# design.net
KiCad netlist of a schematic drawn in Altium Designer
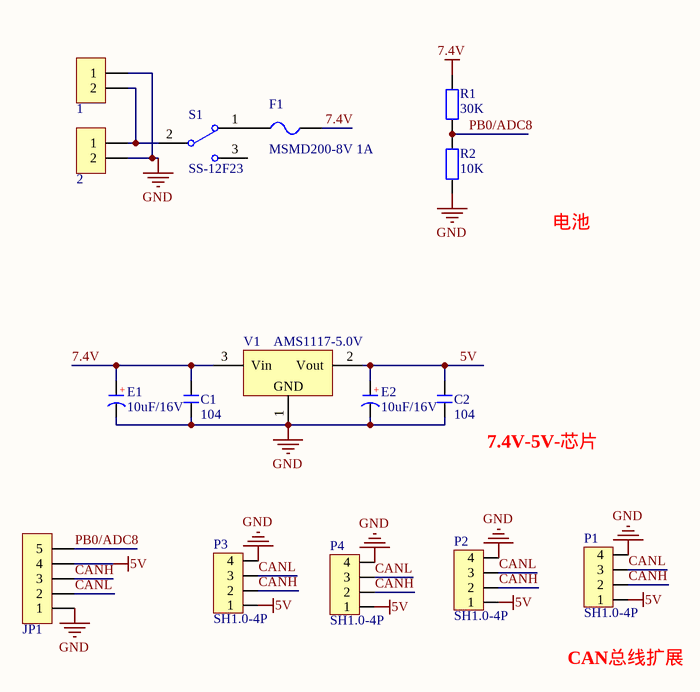
[diagram p0: 电源板.SchDoc]

(export (version "E")
  (design (tool "Eeschema 10.0.6"))
  (components
    (comp (ref "1")
      (value "HDR-1X2")
      (footprint "XH2.54-WI-2P")
      (description "2P接插件")
      (fields (field (name "版权归属") "封装库来自淘宝 ID：黄晶宝石"))
      (libsource (lib "5.3 - 接插件-脚距2.54 (100mil) ") (part "Header 2"))
    )
    (comp (ref "2")
      (value "HDR-1X2")
      (footprint "XH2.54-WI-2P")
      (description "2P接插件")
      (fields (field (name "版权归属") "封装库来自淘宝 ID：黄晶宝石"))
      (libsource (lib "5.3 - 接插件-脚距2.54 (100mil) ") (part "Header 2"))
    )
    (comp (ref "C1")
      (value "104")
      (footprint "C 0603_L")
      (description "贴片电容")
      (libsource (lib "0.1 - 电阻-电容-电感") (part "C"))
    )
    (comp (ref "C2")
      (value "104")
      (footprint "C 0603_L")
      (description "贴片电容")
      (libsource (lib "0.1 - 电阻-电容-电感") (part "C"))
    )
    (comp (ref "E1")
      (value "10uF/16V")
      (footprint "CD A(3216)")
      (description "贴片钽电容")
      (libsource (lib "0.1 - 电阻-电容-电感") (part "CT"))
    )
    (comp (ref "E2")
      (value "10uF/16V")
      (footprint "CD A(3216)")
      (description "贴片钽电容")
      (libsource (lib "0.1 - 电阻-电容-电感") (part "CT"))
    )
    (comp (ref "F1")
      (value "MSMD200-8V 1A")
      (footprint "FU 1206")
      (description "贴片保险丝")
      (fields (field (name "版权归属") "封装库来自淘宝卖家 ID：黄晶宝石"))
      (libsource (lib "2.0 - 保险丝-晶振-光耦") (part "FU"))
    )
    (comp (ref "JP1")
      (value "HDR-1X5")
      (footprint "HDR2.54-LI-5P")
      (description "5P接插件")
      (fields (field (name "版权归属") "封装库来自淘宝 ID：黄晶宝石"))
      (libsource (lib "5.3 - 接插件-脚距2.54 (100mil) ") (part "Header 5"))
    )
    (comp (ref "P1") (value "SH1.0-4P") (footprint "SH1.0-4P") (libsource (lib "SH1.0") (part "SH1.0-4P")))
    (comp (ref "P2") (value "SH1.0-4P") (footprint "SH1.0-4P") (libsource (lib "SH1.0") (part "SH1.0-4P")))
    (comp (ref "P3") (value "SH1.0-4P") (footprint "SH1.0-4P") (libsource (lib "SH1.0") (part "SH1.0-4P")))
    (comp (ref "P4") (value "SH1.0-4P") (footprint "SH1.0-4P") (libsource (lib "SH1.0") (part "SH1.0-4P")))
    (comp (ref "R1")
      (value "30K")
      (footprint "R 0603_L")
      (description "贴片电阻")
      (fields (field (name "版权归属") "来自淘宝 ID：黄晶宝石"))
      (libsource (lib "0.1 - 电阻-电容-电感") (part "R"))
    )
    (comp (ref "R2")
      (value "10K")
      (footprint "R 0603_L")
      (description "贴片电阻")
      (fields (field (name "版权归属") "来自淘宝 ID：黄晶宝石"))
      (libsource (lib "0.1 - 电阻-电容-电感") (part "R"))
    )
    (comp (ref "S1")
      (value "SS-12F23")
      (footprint "SK-12D07VG3")
      (description "1路波动开关")
      (fields (field (name "版权归属") "源创客"))
      (libsource (lib "按键-开关") (part "SSW-1P"))
    )
    (comp (ref "V1")
      (value "AMS1117-5.0V")
      (footprint "SOT223_L")
      (description "三端稳压芯片")
      (libsource (lib "1.1 - 电源类芯片") (part "AMS1117"))
    )
  )
  (nets
    (net (code "1") (name "/CANH") (class "Default")
      (node (ref "JP1") (pin "3") (pinfunction "3_3") (pintype "passive"))
      (node (ref "P1") (pin "2") (pinfunction "2_2") (pintype "passive"))
      (node (ref "P2") (pin "2") (pinfunction "2_2") (pintype "passive"))
      (node (ref "P3") (pin "2") (pinfunction "2_2") (pintype "passive"))
      (node (ref "P4") (pin "2") (pinfunction "2_2") (pintype "passive"))
    )
    (net (code "2") (name "/CANL") (class "Default")
      (node (ref "JP1") (pin "2") (pinfunction "2_2") (pintype "passive"))
      (node (ref "P1") (pin "3") (pinfunction "3_3") (pintype "passive"))
      (node (ref "P2") (pin "3") (pinfunction "3_3") (pintype "passive"))
      (node (ref "P3") (pin "3") (pinfunction "3_3") (pintype "passive"))
      (node (ref "P4") (pin "3") (pinfunction "3_3") (pintype "passive"))
    )
    (net (code "3") (name "/PB0{slash}ADC8") (class "Default")
      (node (ref "JP1") (pin "5") (pinfunction "5_5") (pintype "passive"))
      (node (ref "R1") (pin "1") (pinfunction "1_1") (pintype "passive"))
      (node (ref "R2") (pin "2") (pinfunction "2_2") (pintype "passive"))
    )
    (net (code "4") (name "5V") (class "Default")
      (node (ref "C2") (pin "2") (pinfunction "2_2") (pintype "passive"))
      (node (ref "E2") (pin "1") (pinfunction "A_1") (pintype "passive"))
      (node (ref "JP1") (pin "4") (pinfunction "4_4") (pintype "passive"))
      (node (ref "P1") (pin "1") (pinfunction "1_1") (pintype "passive"))
      (node (ref "P2") (pin "1") (pinfunction "1_1") (pintype "passive"))
      (node (ref "P3") (pin "1") (pinfunction "1_1") (pintype "passive"))
      (node (ref "P4") (pin "1") (pinfunction "1_1") (pintype "passive"))
      (node (ref "V1") (pin "2") (pinfunction "Vout_2") (pintype "passive"))
    )
    (net (code "5") (name "7.4V") (class "Default")
      (node (ref "C1") (pin "2") (pinfunction "2_2") (pintype "passive"))
      (node (ref "E1") (pin "1") (pinfunction "A_1") (pintype "passive"))
      (node (ref "F1") (pin "2") (pinfunction "2_2") (pintype "passive"))
      (node (ref "R1") (pin "2") (pinfunction "2_2") (pintype "passive"))
      (node (ref "V1") (pin "3") (pinfunction "Vin_3") (pintype "passive"))
    )
    (net (code "6") (name "GND") (class "Default")
      (node (ref "1") (pin "1") (pinfunction "1_1") (pintype "passive"))
      (node (ref "2") (pin "2") (pinfunction "2_2") (pintype "passive"))
      (node (ref "C1") (pin "1") (pinfunction "1_1") (pintype "passive"))
      (node (ref "C2") (pin "1") (pinfunction "1_1") (pintype "passive"))
      (node (ref "E1") (pin "2") (pinfunction "K_2") (pintype "passive"))
      (node (ref "E2") (pin "2") (pinfunction "K_2") (pintype "passive"))
      (node (ref "JP1") (pin "1") (pinfunction "1_1") (pintype "passive"))
      (node (ref "P1") (pin "4") (pinfunction "4_4") (pintype "passive"))
      (node (ref "P2") (pin "4") (pinfunction "4_4") (pintype "passive"))
      (node (ref "P3") (pin "4") (pinfunction "4_4") (pintype "passive"))
      (node (ref "P4") (pin "4") (pinfunction "4_4") (pintype "passive"))
      (node (ref "R2") (pin "1") (pinfunction "1_1") (pintype "passive"))
      (node (ref "V1") (pin "1") (pinfunction "GND_1") (pintype "passive"))
    )
    (net (code "7") (name "Net-(1-Pad2)") (class "Default")
      (node (ref "1") (pin "2") (pinfunction "2_2") (pintype "passive"))
      (node (ref "2") (pin "1") (pinfunction "1_1") (pintype "passive"))
      (node (ref "S1") (pin "2") (pinfunction "2_2") (pintype "passive"))
    )
    (net (code "8") (name "Net-(F1-Pad1)") (class "Default")
      (node (ref "F1") (pin "1") (pinfunction "1_1") (pintype "passive"))
      (node (ref "S1") (pin "1") (pinfunction "1_1") (pintype "passive"))
    )
    (net (code "9") (name "unconnected-(S1-Pad3)") (class "Default")
      (node (ref "S1") (pin "3") (pinfunction "3_3") (pintype "passive"))
    )
  )
)
